# smog_v1_1_brain.net
KiCad netlist of a schematic drawn in EAGLE
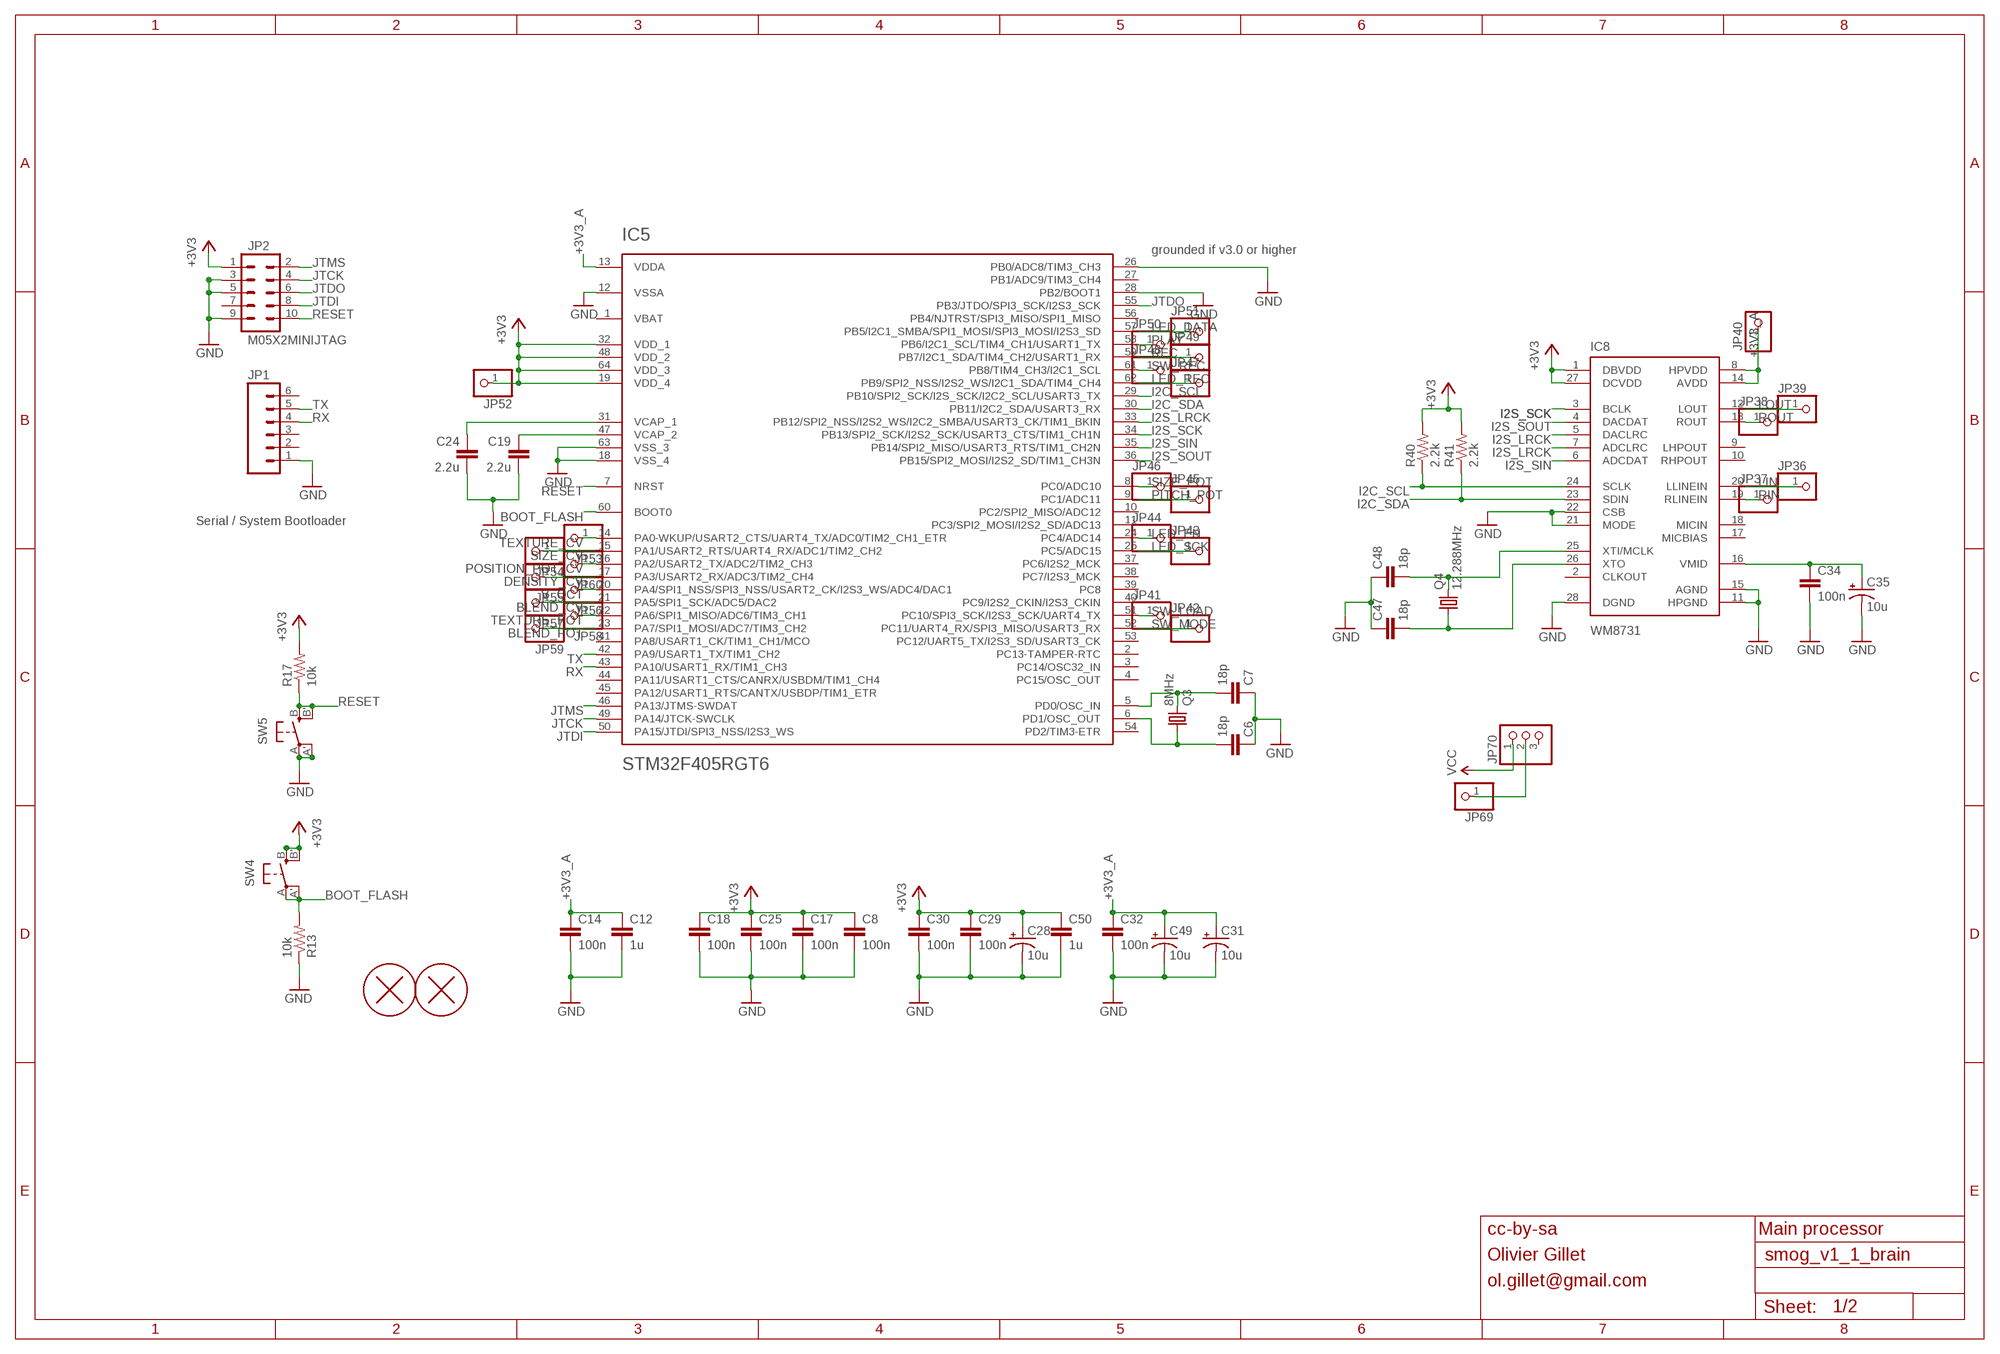
[diagram p0: schematic, sheet 1]
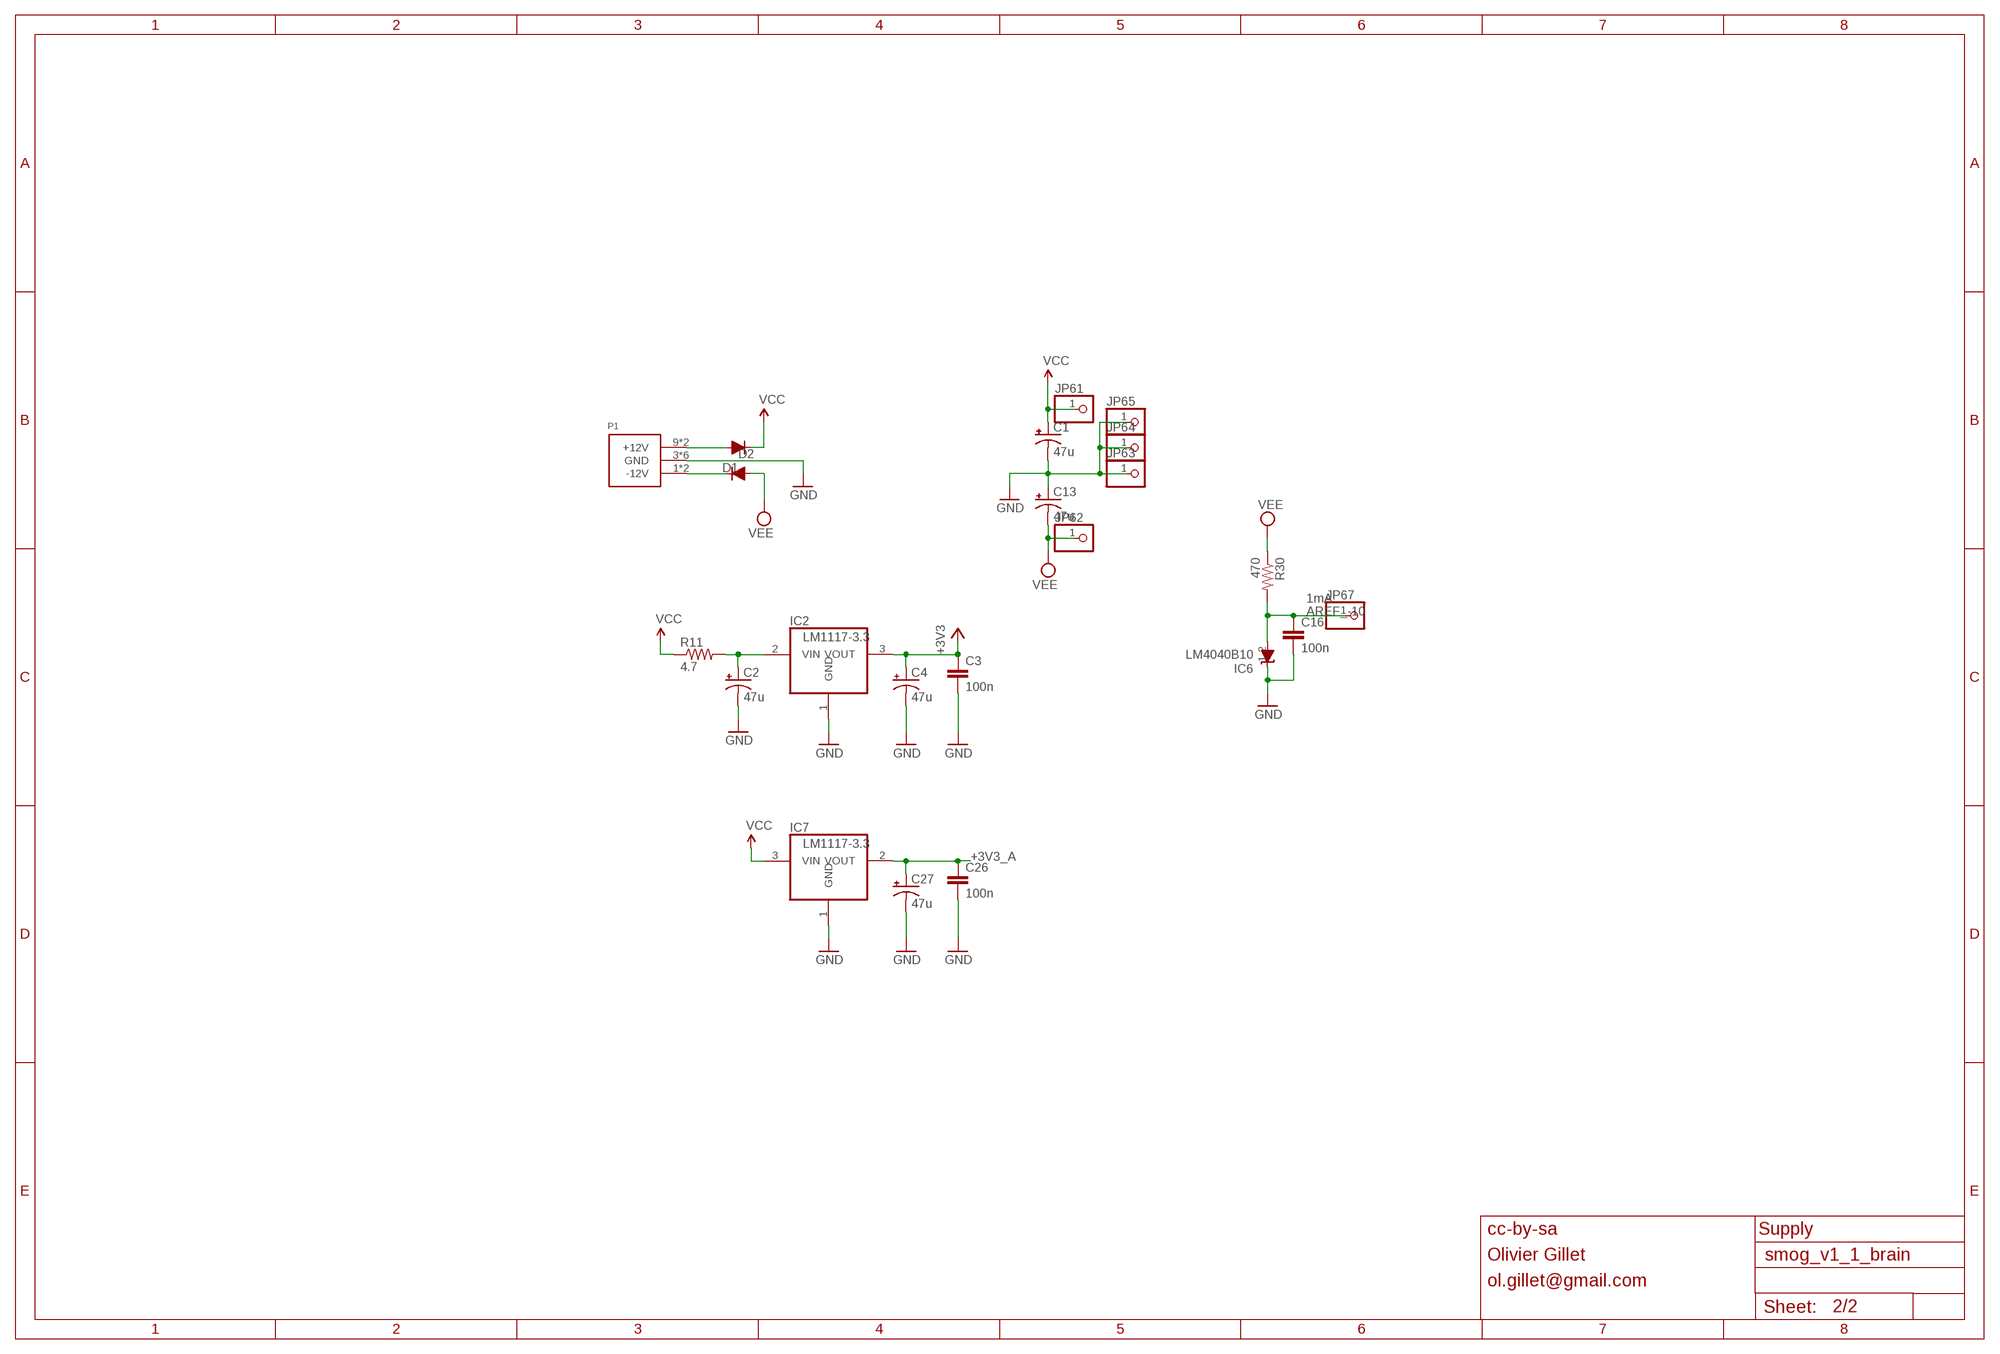
[diagram p1: schematic, sheet 2]

(export (version "E")
  (design (tool "Eeschema 10.0.6"))
  (components
    (comp (ref "C1")
      (value "47u")
      (footprint "eagle-import:PANASONIC_D")
      (libsource (lib "eagle-import") (part "CAP_POLD"))
    )
    (comp (ref "C2")
      (value "47u")
      (footprint "eagle-import:PANASONIC_D")
      (libsource (lib "eagle-import") (part "CAP_POLD"))
    )
    (comp (ref "C3")
      (value "100n")
      (footprint "eagle-import:RESISTOR_0603")
      (libsource (lib "eagle-import") (part "CAPACITOR"))
    )
    (comp (ref "C4")
      (value "47u")
      (footprint "eagle-import:PANASONIC_D")
      (libsource (lib "eagle-import") (part "CAP_POLD"))
    )
    (comp (ref "C13")
      (value "47u")
      (footprint "eagle-import:PANASONIC_D")
      (libsource (lib "eagle-import") (part "CAP_POLD"))
    )
    (comp (ref "C16")
      (value "100n")
      (footprint "eagle-import:RESISTOR_0603")
      (libsource (lib "eagle-import") (part "CAPACITOR"))
    )
    (comp (ref "C26")
      (value "100n")
      (footprint "eagle-import:RESISTOR_0603")
      (libsource (lib "eagle-import") (part "CAPACITOR"))
    )
    (comp (ref "C27")
      (value "47u")
      (footprint "eagle-import:PANASONIC_D")
      (libsource (lib "eagle-import") (part "CAP_POLD"))
    )
    (comp (ref "D1")
      (value "1N5819HW")
      (footprint "eagle-import:SOD123")
      (libsource (lib "eagle-import") (part "DIODE"))
    )
    (comp (ref "D2")
      (value "1N5819HW")
      (footprint "eagle-import:SOD123")
      (libsource (lib "eagle-import") (part "DIODE"))
    )
    (comp (ref "IC2")
      (value "LM1117-3.3")
      (footprint "eagle-import:TO252")
      (libsource (lib "eagle-import") (part "REG1117T"))
    )
    (comp (ref "IC6")
      (value "LM4040B10")
      (footprint "eagle-import:SOT23")
      (libsource (lib "eagle-import") (part "LM4040SOT23"))
    )
    (comp (ref "IC7")
      (value "LM1117-3.3")
      (footprint "eagle-import:SOT223")
      (libsource (lib "eagle-import") (part "REG1117"))
    )
    (comp (ref "JP61")
      (value "PINHD-1X1")
      (footprint "eagle-import:1X01")
      (libsource (lib "eagle-import") (part "PINHD-1X1"))
    )
    (comp (ref "JP62")
      (value "PINHD-1X1")
      (footprint "eagle-import:1X01")
      (libsource (lib "eagle-import") (part "PINHD-1X1"))
    )
    (comp (ref "JP63")
      (value "PINHD-1X1")
      (footprint "eagle-import:1X01")
      (libsource (lib "eagle-import") (part "PINHD-1X1"))
    )
    (comp (ref "JP64")
      (value "PINHD-1X1")
      (footprint "eagle-import:1X01")
      (libsource (lib "eagle-import") (part "PINHD-1X1"))
    )
    (comp (ref "JP65")
      (value "PINHD-1X1")
      (footprint "eagle-import:1X01")
      (libsource (lib "eagle-import") (part "PINHD-1X1"))
    )
    (comp (ref "JP67")
      (value "PINHD-1X1")
      (footprint "eagle-import:1X01")
      (libsource (lib "eagle-import") (part "PINHD-1X1"))
    )
    (comp (ref "P1")
      (value "POWER_SIMPLE10")
      (footprint "eagle-import:POWER_10")
      (libsource (lib "eagle-import") (part "POWER_SIMPLE10"))
    )
    (comp (ref "R11")
      (value "4.7")
      (footprint "eagle-import:RESISTOR_0603")
      (libsource (lib "eagle-import") (part "RESISTOR"))
    )
    (comp (ref "R30")
      (value "470")
      (footprint "eagle-import:RESISTOR_0603")
      (libsource (lib "eagle-import") (part "RESISTOR"))
    )
    (comp (ref "C6")
      (value "18p")
      (footprint "eagle-import:RESISTOR_0603")
      (libsource (lib "eagle-import") (part "CAPACITOR"))
    )
    (comp (ref "C7")
      (value "18p")
      (footprint "eagle-import:RESISTOR_0603")
      (libsource (lib "eagle-import") (part "CAPACITOR"))
    )
    (comp (ref "C8")
      (value "100n")
      (footprint "eagle-import:RESISTOR_0603")
      (libsource (lib "eagle-import") (part "CAPACITOR"))
    )
    (comp (ref "C12")
      (value "1u")
      (footprint "eagle-import:RESISTOR_0603")
      (libsource (lib "eagle-import") (part "CAPACITOR"))
    )
    (comp (ref "C14")
      (value "100n")
      (footprint "eagle-import:RESISTOR_0603")
      (libsource (lib "eagle-import") (part "CAPACITOR"))
    )
    (comp (ref "C17")
      (value "100n")
      (footprint "eagle-import:RESISTOR_0603")
      (libsource (lib "eagle-import") (part "CAPACITOR"))
    )
    (comp (ref "C18")
      (value "100n")
      (footprint "eagle-import:RESISTOR_0603")
      (libsource (lib "eagle-import") (part "CAPACITOR"))
    )
    (comp (ref "C19")
      (value "2.2u")
      (footprint "eagle-import:RESISTOR_0603")
      (libsource (lib "eagle-import") (part "CAPACITOR"))
    )
    (comp (ref "C24")
      (value "2.2u")
      (footprint "eagle-import:RESISTOR_0603")
      (libsource (lib "eagle-import") (part "CAPACITOR"))
    )
    (comp (ref "C25")
      (value "100n")
      (footprint "eagle-import:RESISTOR_0603")
      (libsource (lib "eagle-import") (part "CAPACITOR"))
    )
    (comp (ref "C28")
      (value "10u")
      (footprint "eagle-import:PANASONIC_B")
      (libsource (lib "eagle-import") (part "CAP_POL"))
    )
    (comp (ref "C29")
      (value "100n")
      (footprint "eagle-import:RESISTOR_0603")
      (libsource (lib "eagle-import") (part "CAPACITOR"))
    )
    (comp (ref "C30")
      (value "100n")
      (footprint "eagle-import:RESISTOR_0603")
      (libsource (lib "eagle-import") (part "CAPACITOR"))
    )
    (comp (ref "C31")
      (value "10u")
      (footprint "eagle-import:PANASONIC_B")
      (libsource (lib "eagle-import") (part "CAP_POL"))
    )
    (comp (ref "C32")
      (value "100n")
      (footprint "eagle-import:RESISTOR_0603")
      (libsource (lib "eagle-import") (part "CAPACITOR"))
    )
    (comp (ref "C34")
      (value "100n")
      (footprint "eagle-import:RESISTOR_0603")
      (libsource (lib "eagle-import") (part "CAPACITOR"))
    )
    (comp (ref "C35")
      (value "10u")
      (footprint "eagle-import:PANASONIC_B")
      (libsource (lib "eagle-import") (part "CAP_POL"))
    )
    (comp (ref "C47")
      (value "18p")
      (footprint "eagle-import:RESISTOR_0603")
      (libsource (lib "eagle-import") (part "CAPACITOR"))
    )
    (comp (ref "C48")
      (value "18p")
      (footprint "eagle-import:RESISTOR_0603")
      (libsource (lib "eagle-import") (part "CAPACITOR"))
    )
    (comp (ref "C49")
      (value "10u")
      (footprint "eagle-import:PANASONIC_B")
      (libsource (lib "eagle-import") (part "CAP_POL"))
    )
    (comp (ref "C50")
      (value "1u")
      (footprint "eagle-import:RESISTOR_0603")
      (libsource (lib "eagle-import") (part "CAPACITOR"))
    )
    (comp (ref "H1")
      (value "PCB_SCREW")
      (footprint "eagle-import:PCB_SCREW")
      (libsource (lib "eagle-import") (part "PCB_SCREW"))
    )
    (comp (ref "H2")
      (value "PCB_SCREW")
      (footprint "eagle-import:PCB_SCREW")
      (libsource (lib "eagle-import") (part "PCB_SCREW"))
    )
    (comp (ref "IC5")
      (value "STM32F405RGT6")
      (footprint "eagle-import:TQFP-10X10-64")
      (libsource (lib "eagle-import") (part "STM32F20X"))
    )
    (comp (ref "IC8")
      (value "WM8731")
      (footprint "eagle-import:SSOP28")
      (libsource (lib "eagle-import") (part "WM8731"))
    )
    (comp (ref "JP1")
      (value "M06SIP")
      (footprint "eagle-import:1X06")
      (libsource (lib "eagle-import") (part "M06SIP"))
    )
    (comp (ref "JP2")
      (value "M05X2MINIJTAG")
      (footprint "eagle-import:2X5-1.27")
      (libsource (lib "eagle-import") (part "M05X2MINIJTAG"))
    )
    (comp (ref "JP36")
      (value "PINHD-1X1")
      (footprint "eagle-import:1X01")
      (libsource (lib "eagle-import") (part "PINHD-1X1"))
    )
    (comp (ref "JP37")
      (value "PINHD-1X1")
      (footprint "eagle-import:1X01")
      (libsource (lib "eagle-import") (part "PINHD-1X1"))
    )
    (comp (ref "JP38")
      (value "PINHD-1X1")
      (footprint "eagle-import:1X01")
      (libsource (lib "eagle-import") (part "PINHD-1X1"))
    )
    (comp (ref "JP39")
      (value "PINHD-1X1")
      (footprint "eagle-import:1X01")
      (libsource (lib "eagle-import") (part "PINHD-1X1"))
    )
    (comp (ref "JP40")
      (value "PINHD-1X1")
      (footprint "eagle-import:1X01")
      (libsource (lib "eagle-import") (part "PINHD-1X1"))
    )
    (comp (ref "JP41")
      (value "PINHD-1X1")
      (footprint "eagle-import:1X01")
      (libsource (lib "eagle-import") (part "PINHD-1X1"))
    )
    (comp (ref "JP42")
      (value "PINHD-1X1")
      (footprint "eagle-import:1X01")
      (libsource (lib "eagle-import") (part "PINHD-1X1"))
    )
    (comp (ref "JP43")
      (value "PINHD-1X1")
      (footprint "eagle-import:1X01")
      (libsource (lib "eagle-import") (part "PINHD-1X1"))
    )
    (comp (ref "JP44")
      (value "PINHD-1X1")
      (footprint "eagle-import:1X01")
      (libsource (lib "eagle-import") (part "PINHD-1X1"))
    )
    (comp (ref "JP45")
      (value "PINHD-1X1")
      (footprint "eagle-import:1X01")
      (libsource (lib "eagle-import") (part "PINHD-1X1"))
    )
    (comp (ref "JP46")
      (value "PINHD-1X1")
      (footprint "eagle-import:1X01")
      (libsource (lib "eagle-import") (part "PINHD-1X1"))
    )
    (comp (ref "JP47")
      (value "PINHD-1X1")
      (footprint "eagle-import:1X01")
      (libsource (lib "eagle-import") (part "PINHD-1X1"))
    )
    (comp (ref "JP48")
      (value "PINHD-1X1")
      (footprint "eagle-import:1X01")
      (libsource (lib "eagle-import") (part "PINHD-1X1"))
    )
    (comp (ref "JP49")
      (value "PINHD-1X1")
      (footprint "eagle-import:1X01")
      (libsource (lib "eagle-import") (part "PINHD-1X1"))
    )
    (comp (ref "JP50")
      (value "PINHD-1X1")
      (footprint "eagle-import:1X01")
      (libsource (lib "eagle-import") (part "PINHD-1X1"))
    )
    (comp (ref "JP51")
      (value "PINHD-1X1")
      (footprint "eagle-import:1X01")
      (libsource (lib "eagle-import") (part "PINHD-1X1"))
    )
    (comp (ref "JP52")
      (value "PINHD-1X1")
      (footprint "eagle-import:1X01")
      (libsource (lib "eagle-import") (part "PINHD-1X1"))
    )
    (comp (ref "JP53")
      (value "PINHD-1X1")
      (footprint "eagle-import:1X01")
      (libsource (lib "eagle-import") (part "PINHD-1X1"))
    )
    (comp (ref "JP54")
      (value "PINHD-1X1")
      (footprint "eagle-import:1X01")
      (libsource (lib "eagle-import") (part "PINHD-1X1"))
    )
    (comp (ref "JP55")
      (value "PINHD-1X1")
      (footprint "eagle-import:1X01")
      (libsource (lib "eagle-import") (part "PINHD-1X1"))
    )
    (comp (ref "JP56")
      (value "PINHD-1X1")
      (footprint "eagle-import:1X01")
      (libsource (lib "eagle-import") (part "PINHD-1X1"))
    )
    (comp (ref "JP57")
      (value "PINHD-1X1")
      (footprint "eagle-import:1X01")
      (libsource (lib "eagle-import") (part "PINHD-1X1"))
    )
    (comp (ref "JP58")
      (value "PINHD-1X1")
      (footprint "eagle-import:1X01")
      (libsource (lib "eagle-import") (part "PINHD-1X1"))
    )
    (comp (ref "JP59")
      (value "PINHD-1X1")
      (footprint "eagle-import:1X01")
      (libsource (lib "eagle-import") (part "PINHD-1X1"))
    )
    (comp (ref "JP60")
      (value "PINHD-1X1")
      (footprint "eagle-import:1X01")
      (libsource (lib "eagle-import") (part "PINHD-1X1"))
    )
    (comp (ref "JP69")
      (value "PINHD-1X1")
      (footprint "eagle-import:1X01")
      (libsource (lib "eagle-import") (part "PINHD-1X1"))
    )
    (comp (ref "JP70")
      (value "PINHD-1X3")
      (footprint "eagle-import:1X03")
      (libsource (lib "eagle-import") (part "PINHD-1X3"))
    )
    (comp (ref "Q3")
      (value "8MHz")
      (footprint "eagle-import:HC49UP")
      (libsource (lib "eagle-import") (part "CRYSTAL"))
    )
    (comp (ref "Q4")
      (value "12.288MHz")
      (footprint "eagle-import:HC49UP")
      (libsource (lib "eagle-import") (part "CRYSTAL"))
    )
    (comp (ref "R13")
      (value "10k")
      (footprint "eagle-import:RESISTOR_0603")
      (libsource (lib "eagle-import") (part "RESISTOR"))
    )
    (comp (ref "R17")
      (value "10k")
      (footprint "eagle-import:RESISTOR_0603")
      (libsource (lib "eagle-import") (part "RESISTOR"))
    )
    (comp (ref "R40")
      (value "2.2k")
      (footprint "eagle-import:RESISTOR_0603")
      (libsource (lib "eagle-import") (part "RESISTOR"))
    )
    (comp (ref "R41")
      (value "2.2k")
      (footprint "eagle-import:RESISTOR_0603")
      (libsource (lib "eagle-import") (part "RESISTOR"))
    )
    (comp (ref "SW4")
      (value "EVQQ2")
      (footprint "eagle-import:EVQ-Q2")
      (libsource (lib "eagle-import") (part "EVQQ2"))
    )
    (comp (ref "SW5")
      (value "EVQQ2")
      (footprint "eagle-import:EVQ-Q2")
      (libsource (lib "eagle-import") (part "EVQQ2"))
    )
  )
  (nets
    (net (code "1") (name "+3V3") (class "Default")
      (node (ref "C17") (pin "1") (pinfunction "1_1") (pintype "passive"))
      (node (ref "C18") (pin "1") (pinfunction "1_1") (pintype "passive"))
      (node (ref "C25") (pin "1") (pinfunction "1_1") (pintype "passive"))
      (node (ref "C28") (pin "+") (pinfunction "+_+") (pintype "passive"))
      (node (ref "C29") (pin "1") (pinfunction "1_1") (pintype "passive"))
      (node (ref "C3") (pin "1") (pinfunction "1_1") (pintype "passive"))
      (node (ref "C30") (pin "1") (pinfunction "1_1") (pintype "passive"))
      (node (ref "C4") (pin "+") (pinfunction "+_+") (pintype "passive"))
      (node (ref "C50") (pin "1") (pinfunction "1_1") (pintype "passive"))
      (node (ref "C8") (pin "1") (pinfunction "1_1") (pintype "passive"))
      (node (ref "IC2") (pin "3") (pinfunction "VOUT_3") (pintype "output"))
      (node (ref "IC5") (pin "19") (pinfunction "VDD_4_19") (pintype "power_in"))
      (node (ref "IC5") (pin "32") (pinfunction "VDD_1_32") (pintype "power_in"))
      (node (ref "IC5") (pin "48") (pinfunction "VDD_2_48") (pintype "power_in"))
      (node (ref "IC5") (pin "64") (pinfunction "VDD_3_64") (pintype "power_in"))
      (node (ref "IC8") (pin "1") (pinfunction "DBVDD_1") (pintype "bidirectional"))
      (node (ref "IC8") (pin "27") (pinfunction "DCVDD_27") (pintype "bidirectional"))
      (node (ref "JP2") (pin "1") (pinfunction "1_1") (pintype "passive"))
      (node (ref "JP52") (pin "1") (pinfunction "1_1") (pintype "passive"))
      (node (ref "R17") (pin "2") (pinfunction "2_2") (pintype "passive"))
      (node (ref "R40") (pin "2") (pinfunction "2_2") (pintype "passive"))
      (node (ref "R41") (pin "2") (pinfunction "2_2") (pintype "passive"))
      (node (ref "SW4") (pin "B") (pinfunction "S_B") (pintype "passive"))
      (node (ref "SW4") (pin "B'") (pinfunction "S1_B'") (pintype "passive"))
    )
    (net (code "2") (name "+3V3_A") (class "Default")
      (node (ref "C12") (pin "1") (pinfunction "1_1") (pintype "passive"))
      (node (ref "C14") (pin "1") (pinfunction "1_1") (pintype "passive"))
      (node (ref "C26") (pin "1") (pinfunction "1_1") (pintype "passive"))
      (node (ref "C27") (pin "+") (pinfunction "+_+") (pintype "passive"))
      (node (ref "C31") (pin "+") (pinfunction "+_+") (pintype "passive"))
      (node (ref "C32") (pin "1") (pinfunction "1_1") (pintype "passive"))
      (node (ref "C49") (pin "+") (pinfunction "+_+") (pintype "passive"))
      (node (ref "IC5") (pin "13") (pinfunction "VDDA_13") (pintype "power_in"))
      (node (ref "IC7") (pin "2") (pinfunction "VOUT_2") (pintype "output"))
      (node (ref "IC8") (pin "14") (pinfunction "AVDD_14") (pintype "bidirectional"))
      (node (ref "IC8") (pin "8") (pinfunction "HPVDD_8") (pintype "bidirectional"))
      (node (ref "JP40") (pin "1") (pinfunction "1_1") (pintype "passive"))
    )
    (net (code "3") (name "AREF_-10") (class "Default")
      (node (ref "C16") (pin "1") (pinfunction "1_1") (pintype "passive"))
      (node (ref "IC6") (pin "2") (pinfunction "A_2") (pintype "passive"))
      (node (ref "JP67") (pin "1") (pinfunction "1_1") (pintype "passive"))
      (node (ref "R30") (pin "2") (pinfunction "2_2") (pintype "passive"))
    )
    (net (code "4") (name "BLEND_CV") (class "Default")
      (node (ref "IC5") (pin "21") (pinfunction "PA5/SPI1_SCK/ADC5/DAC2_21") (pintype "bidirectional"))
      (node (ref "JP57") (pin "1") (pinfunction "1_1") (pintype "passive"))
    )
    (net (code "5") (name "BLEND_POT") (class "Default")
      (node (ref "IC5") (pin "23") (pinfunction "PA7/SPI1_MOSI/ADC7/TIM3_CH2_23") (pintype "bidirectional"))
      (node (ref "JP59") (pin "1") (pinfunction "1_1") (pintype "passive"))
    )
    (net (code "6") (name "BOOT_FLASH") (class "Default")
      (node (ref "IC5") (pin "60") (pinfunction "BOOT0_60") (pintype "bidirectional"))
      (node (ref "R13") (pin "2") (pinfunction "2_2") (pintype "passive"))
      (node (ref "SW4") (pin "A") (pinfunction "P_A") (pintype "passive"))
      (node (ref "SW4") (pin "A'") (pinfunction "P1_A'") (pintype "passive"))
    )
    (net (code "7") (name "DENSITY_CV") (class "Default")
      (node (ref "IC5") (pin "17") (pinfunction "PA3/USART2_RX/ADC3/TIM2_CH4_17") (pintype "bidirectional"))
      (node (ref "JP55") (pin "1") (pinfunction "1_1") (pintype "passive"))
    )
    (net (code "8") (name "GND") (class "Default")
      (node (ref "C1") (pin "-") (pinfunction "-_-") (pintype "passive"))
      (node (ref "C12") (pin "2") (pinfunction "2_2") (pintype "passive"))
      (node (ref "C13") (pin "+") (pinfunction "+_+") (pintype "passive"))
      (node (ref "C14") (pin "2") (pinfunction "2_2") (pintype "passive"))
      (node (ref "C16") (pin "2") (pinfunction "2_2") (pintype "passive"))
      (node (ref "C17") (pin "2") (pinfunction "2_2") (pintype "passive"))
      (node (ref "C18") (pin "2") (pinfunction "2_2") (pintype "passive"))
      (node (ref "C19") (pin "2") (pinfunction "2_2") (pintype "passive"))
      (node (ref "C2") (pin "-") (pinfunction "-_-") (pintype "passive"))
      (node (ref "C24") (pin "2") (pinfunction "2_2") (pintype "passive"))
      (node (ref "C25") (pin "2") (pinfunction "2_2") (pintype "passive"))
      (node (ref "C26") (pin "2") (pinfunction "2_2") (pintype "passive"))
      (node (ref "C27") (pin "-") (pinfunction "-_-") (pintype "passive"))
      (node (ref "C28") (pin "-") (pinfunction "-_-") (pintype "passive"))
      (node (ref "C29") (pin "2") (pinfunction "2_2") (pintype "passive"))
      (node (ref "C3") (pin "2") (pinfunction "2_2") (pintype "passive"))
      (node (ref "C30") (pin "2") (pinfunction "2_2") (pintype "passive"))
      (node (ref "C31") (pin "-") (pinfunction "-_-") (pintype "passive"))
      (node (ref "C32") (pin "2") (pinfunction "2_2") (pintype "passive"))
      (node (ref "C34") (pin "2") (pinfunction "2_2") (pintype "passive"))
      (node (ref "C35") (pin "-") (pinfunction "-_-") (pintype "passive"))
      (node (ref "C4") (pin "-") (pinfunction "-_-") (pintype "passive"))
      (node (ref "C47") (pin "1") (pinfunction "1_1") (pintype "passive"))
      (node (ref "C48") (pin "1") (pinfunction "1_1") (pintype "passive"))
      (node (ref "C49") (pin "-") (pinfunction "-_-") (pintype "passive"))
      (node (ref "C50") (pin "2") (pinfunction "2_2") (pintype "passive"))
      (node (ref "C6") (pin "1") (pinfunction "1_1") (pintype "passive"))
      (node (ref "C7") (pin "1") (pinfunction "1_1") (pintype "passive"))
      (node (ref "C8") (pin "2") (pinfunction "2_2") (pintype "passive"))
      (node (ref "IC2") (pin "1") (pinfunction "GND_1") (pintype "power_in"))
      (node (ref "IC5") (pin "12") (pinfunction "VSSA_12") (pintype "power_in"))
      (node (ref "IC5") (pin "18") (pinfunction "VSS_4_18") (pintype "power_in"))
      (node (ref "IC5") (pin "26") (pinfunction "PB0/ADC8/TIM3_CH3_26") (pintype "bidirectional"))
      (node (ref "IC5") (pin "28") (pinfunction "PB2/BOOT1_28") (pintype "bidirectional"))
      (node (ref "IC5") (pin "63") (pinfunction "VSS_3_63") (pintype "power_in"))
      (node (ref "IC6") (pin "1") (pinfunction "C_1") (pintype "passive"))
      (node (ref "IC7") (pin "1") (pinfunction "GND_1") (pintype "power_in"))
      (node (ref "IC8") (pin "11") (pinfunction "HPGND_11") (pintype "bidirectional"))
      (node (ref "IC8") (pin "15") (pinfunction "AGND_15") (pintype "bidirectional"))
      (node (ref "IC8") (pin "21") (pinfunction "MODE_21") (pintype "bidirectional"))
      (node (ref "IC8") (pin "22") (pinfunction "CSB_22") (pintype "bidirectional"))
      (node (ref "IC8") (pin "28") (pinfunction "DGND_28") (pintype "bidirectional"))
      (node (ref "JP1") (pin "1") (pinfunction "1_1") (pintype "passive"))
      (node (ref "JP2") (pin "3") (pinfunction "3_3") (pintype "passive"))
      (node (ref "JP2") (pin "5") (pinfunction "5_5") (pintype "passive"))
      (node (ref "JP2") (pin "9") (pinfunction "9_9") (pintype "passive"))
      (node (ref "JP63") (pin "1") (pinfunction "1_1") (pintype "passive"))
      (node (ref "JP64") (pin "1") (pinfunction "1_1") (pintype "passive"))
      (node (ref "JP65") (pin "1") (pinfunction "1_1") (pintype "passive"))
      (node (ref "P1") (pin "3") (pinfunction "GND_3") (pintype "bidirectional"))
      (node (ref "P1") (pin "4") (pinfunction "GND_4") (pintype "bidirectional"))
      (node (ref "P1") (pin "5") (pinfunction "GND_5") (pintype "bidirectional"))
      (node (ref "P1") (pin "6") (pinfunction "GND_6") (pintype "bidirectional"))
      (node (ref "P1") (pin "7") (pinfunction "GND_7") (pintype "bidirectional"))
      (node (ref "P1") (pin "8") (pinfunction "GND_8") (pintype "bidirectional"))
      (node (ref "R13") (pin "1") (pinfunction "1_1") (pintype "passive"))
      (node (ref "SW5") (pin "A") (pinfunction "P_A") (pintype "passive"))
      (node (ref "SW5") (pin "A'") (pinfunction "P1_A'") (pintype "passive"))
    )
    (net (code "9") (name "I2C_SCL") (class "Default")
      (node (ref "IC5") (pin "29") (pinfunction "PB10/SPI2_SCK/I2S_SCK/I2C2_SCL/USART3_TX_29") (pintype "bidirectional"))
      (node (ref "IC8") (pin "24") (pinfunction "SCLK_24") (pintype "bidirectional"))
      (node (ref "R40") (pin "1") (pinfunction "1_1") (pintype "passive"))
    )
    (net (code "10") (name "I2C_SDA") (class "Default")
      (node (ref "IC5") (pin "30") (pinfunction "PB11/I2C2_SDA/USART3_RX_30") (pintype "bidirectional"))
      (node (ref "IC8") (pin "23") (pinfunction "SDIN_23") (pintype "bidirectional"))
      (node (ref "R41") (pin "1") (pinfunction "1_1") (pintype "passive"))
    )
    (net (code "11") (name "I2S_LRCK") (class "Default")
      (node (ref "IC5") (pin "33") (pinfunction "PB12/SPI2_NSS/I2S2_WS/I2C2_SMBA/USART3_CK/TIM1_BKIN_33") (pintype "bidirectional"))
      (node (ref "IC8") (pin "5") (pinfunction "DACLRC_5") (pintype "bidirectional"))
      (node (ref "IC8") (pin "7") (pinfunction "ADCLRC_7") (pintype "bidirectional"))
    )
    (net (code "12") (name "I2S_SCK") (class "Default")
      (node (ref "IC5") (pin "34") (pinfunction "PB13/SPI2_SCK/I2S2_SCK/USART3_CTS/TIM1_CH1N_34") (pintype "bidirectional"))
      (node (ref "IC8") (pin "3") (pinfunction "BCLK_3") (pintype "bidirectional"))
    )
    (net (code "13") (name "I2S_SIN") (class "Default")
      (node (ref "IC5") (pin "35") (pinfunction "PB14/SPI2_MISO/USART3_RTS/TIM1_CH2N_35") (pintype "bidirectional"))
      (node (ref "IC8") (pin "6") (pinfunction "ADCDAT_6") (pintype "bidirectional"))
    )
    (net (code "14") (name "I2S_SOUT") (class "Default")
      (node (ref "IC5") (pin "36") (pinfunction "PB15/SPI2_MOSI/I2S2_SD/TIM1_CH3N_36") (pintype "bidirectional"))
      (node (ref "IC8") (pin "4") (pinfunction "DACDAT_4") (pintype "bidirectional"))
    )
    (net (code "15") (name "JTCK") (class "Default")
      (node (ref "IC5") (pin "49") (pinfunction "PA14/JTCK-SWCLK_49") (pintype "bidirectional"))
      (node (ref "JP2") (pin "4") (pinfunction "4_4") (pintype "passive"))
    )
    (net (code "16") (name "JTDI") (class "Default")
      (node (ref "IC5") (pin "50") (pinfunction "PA15/JTDI/SPI3_NSS/I2S3_WS_50") (pintype "bidirectional"))
      (node (ref "JP2") (pin "8") (pinfunction "8_8") (pintype "passive"))
    )
    (net (code "17") (name "JTDO") (class "Default")
      (node (ref "IC5") (pin "55") (pinfunction "PB3/JTDO/SPI3_SCK/I2S3_SCK_55") (pintype "bidirectional"))
      (node (ref "JP2") (pin "6") (pinfunction "6_6") (pintype "passive"))
    )
    (net (code "18") (name "JTMS") (class "Default")
      (node (ref "IC5") (pin "46") (pinfunction "PA13/JTMS-SWDAT_46") (pintype "bidirectional"))
      (node (ref "JP2") (pin "2") (pinfunction "2_2") (pintype "passive"))
    )
    (net (code "19") (name "LED_DATA") (class "Default")
      (node (ref "IC5") (pin "57") (pinfunction "PB5/I2C1_SMBA/SPI1_MOSI/SPI3_MOSI/I2S3_SD_57") (pintype "bidirectional"))
      (node (ref "JP51") (pin "1") (pinfunction "1_1") (pintype "passive"))
    )
    (net (code "20") (name "LED_EN") (class "Default")
      (node (ref "IC5") (pin "24") (pinfunction "PC4/ADC14_24") (pintype "bidirectional"))
      (node (ref "JP44") (pin "1") (pinfunction "1_1") (pintype "passive"))
    )
    (net (code "21") (name "LED_REC") (class "Default")
      (node (ref "IC5") (pin "62") (pinfunction "PB9/SPI2_NSS/I2S2_WS/I2C1_SDA/TIM4_CH4_62") (pintype "bidirectional"))
      (node (ref "JP47") (pin "1") (pinfunction "1_1") (pintype "passive"))
    )
    (net (code "22") (name "LED_SCK") (class "Default")
      (node (ref "IC5") (pin "25") (pinfunction "PC5/ADC15_25") (pintype "bidirectional"))
      (node (ref "JP43") (pin "1") (pinfunction "1_1") (pintype "passive"))
    )
    (net (code "23") (name "LIN") (class "Default")
      (node (ref "IC8") (pin "20") (pinfunction "LLINEIN_20") (pintype "bidirectional"))
      (node (ref "JP36") (pin "1") (pinfunction "1_1") (pintype "passive"))
    )
    (net (code "24") (name "LOUT") (class "Default")
      (node (ref "IC8") (pin "12") (pinfunction "LOUT_12") (pintype "bidirectional"))
      (node (ref "JP39") (pin "1") (pinfunction "1_1") (pintype "passive"))
    )
    (net (code "25") (name "Net-(D1-Pad+)") (class "Default")
      (node (ref "D1") (pin "+") (pinfunction "+_+") (pintype "passive"))
      (node (ref "P1") (pin "10") (pinfunction "+12V_10") (pintype "bidirectional"))
      (node (ref "P1") (pin "9") (pinfunction "+12V_9") (pintype "bidirectional"))
    )
    (net (code "26") (name "Net-(D2-Pad-)") (class "Default")
      (node (ref "D2") (pin "-") (pinfunction "-_-") (pintype "passive"))
      (node (ref "P1") (pin "1") (pinfunction "-12V_1") (pintype "bidirectional"))
      (node (ref "P1") (pin "2") (pinfunction "-12V_2") (pintype "bidirectional"))
    )
    (net (code "27") (name "Net-(IC2-VIN)") (class "Default")
      (node (ref "C2") (pin "+") (pinfunction "+_+") (pintype "passive"))
      (node (ref "IC2") (pin "2") (pinfunction "VIN_2") (pintype "input"))
      (node (ref "R11") (pin "2") (pinfunction "2_2") (pintype "passive"))
    )
    (net (code "28") (name "Net-(IC5-PD0{slash}OSC_IN)") (class "Default")
      (node (ref "C7") (pin "2") (pinfunction "2_2") (pintype "passive"))
      (node (ref "IC5") (pin "5") (pinfunction "PD0/OSC_IN_5") (pintype "bidirectional"))
      (node (ref "Q3") (pin "2") (pinfunction "2_2") (pintype "passive"))
    )
    (net (code "29") (name "Net-(IC5-PD1{slash}OSC_OUT)") (class "Default")
      (node (ref "C6") (pin "2") (pinfunction "2_2") (pintype "passive"))
      (node (ref "IC5") (pin "6") (pinfunction "PD1/OSC_OUT_6") (pintype "bidirectional"))
      (node (ref "Q3") (pin "1") (pinfunction "1_1") (pintype "passive"))
    )
    (net (code "30") (name "Net-(IC5-VCAP_1)") (class "Default")
      (node (ref "C24") (pin "1") (pinfunction "1_1") (pintype "passive"))
      (node (ref "IC5") (pin "31") (pinfunction "VCAP_1_31") (pintype "power_in"))
    )
    (net (code "31") (name "Net-(IC5-VCAP_2)") (class "Default")
      (node (ref "C19") (pin "1") (pinfunction "1_1") (pintype "passive"))
      (node (ref "IC5") (pin "47") (pinfunction "VCAP_2_47") (pintype "power_in"))
    )
    (net (code "32") (name "Net-(IC8-VMID)") (class "Default")
      (node (ref "C34") (pin "1") (pinfunction "1_1") (pintype "passive"))
      (node (ref "C35") (pin "+") (pinfunction "+_+") (pintype "passive"))
      (node (ref "IC8") (pin "16") (pinfunction "VMID_16") (pintype "bidirectional"))
    )
    (net (code "33") (name "Net-(IC8-XTI{slash}MCLK)") (class "Default")
      (node (ref "C48") (pin "2") (pinfunction "2_2") (pintype "passive"))
      (node (ref "IC8") (pin "25") (pinfunction "XTI/MCLK_25") (pintype "bidirectional"))
      (node (ref "Q4") (pin "2") (pinfunction "2_2") (pintype "passive"))
    )
    (net (code "34") (name "Net-(IC8-XTO)") (class "Default")
      (node (ref "C47") (pin "2") (pinfunction "2_2") (pintype "passive"))
      (node (ref "IC8") (pin "26") (pinfunction "XTO_26") (pintype "bidirectional"))
      (node (ref "Q4") (pin "1") (pinfunction "1_1") (pintype "passive"))
    )
    (net (code "35") (name "Net-(JP69-Pad1)") (class "Default")
      (node (ref "JP69") (pin "1") (pinfunction "1_1") (pintype "passive"))
      (node (ref "JP70") (pin "2") (pinfunction "2_2") (pintype "passive"))
    )
    (net (code "36") (name "PITCH_POT") (class "Default")
      (node (ref "IC5") (pin "9") (pinfunction "PC1/ADC11_9") (pintype "bidirectional"))
      (node (ref "JP45") (pin "1") (pinfunction "1_1") (pintype "passive"))
    )
    (net (code "37") (name "PLAY") (class "Default")
      (node (ref "IC5") (pin "58") (pinfunction "PB6/I2C1_SCL/TIM4_CH1/USART1_TX_58") (pintype "bidirectional"))
      (node (ref "JP50") (pin "1") (pinfunction "1_1") (pintype "passive"))
    )
    (net (code "38") (name "POSITION_POT_CV") (class "Default")
      (node (ref "IC5") (pin "16") (pinfunction "PA2/USART2_TX/ADC2/TIM2_CH3_16") (pintype "bidirectional"))
      (node (ref "JP60") (pin "1") (pinfunction "1_1") (pintype "passive"))
    )
    (net (code "39") (name "REC") (class "Default")
      (node (ref "IC5") (pin "59") (pinfunction "PB7/I2C1_SDA/TIM4_CH2/USART1_RX_59") (pintype "bidirectional"))
      (node (ref "JP49") (pin "1") (pinfunction "1_1") (pintype "passive"))
    )
    (net (code "40") (name "RESET") (class "Default")
      (node (ref "IC5") (pin "7") (pinfunction "NRST_7") (pintype "bidirectional"))
      (node (ref "JP2") (pin "10") (pinfunction "10_10") (pintype "passive"))
      (node (ref "R17") (pin "1") (pinfunction "1_1") (pintype "passive"))
      (node (ref "SW5") (pin "B") (pinfunction "S_B") (pintype "passive"))
      (node (ref "SW5") (pin "B'") (pinfunction "S1_B'") (pintype "passive"))
    )
    (net (code "41") (name "RIN") (class "Default")
      (node (ref "IC8") (pin "19") (pinfunction "RLINEIN_19") (pintype "bidirectional"))
      (node (ref "JP37") (pin "1") (pinfunction "1_1") (pintype "passive"))
    )
    (net (code "42") (name "ROUT") (class "Default")
      (node (ref "IC8") (pin "13") (pinfunction "ROUT_13") (pintype "bidirectional"))
      (node (ref "JP38") (pin "1") (pinfunction "1_1") (pintype "passive"))
    )
    (net (code "43") (name "RX") (class "Default")
      (node (ref "IC5") (pin "43") (pinfunction "PA10/USART1_RX/TIM1_CH3_43") (pintype "bidirectional"))
      (node (ref "JP1") (pin "4") (pinfunction "4_4") (pintype "passive"))
    )
    (net (code "44") (name "SIZE_CV") (class "Default")
      (node (ref "IC5") (pin "15") (pinfunction "PA1/USART2_RTS/UART4_RX/ADC1/TIM2_CH2_15") (pintype "bidirectional"))
      (node (ref "JP54") (pin "1") (pinfunction "1_1") (pintype "passive"))
    )
    (net (code "45") (name "SIZE_POT") (class "Default")
      (node (ref "IC5") (pin "8") (pinfunction "PC0/ADC10_8") (pintype "bidirectional"))
      (node (ref "JP46") (pin "1") (pinfunction "1_1") (pintype "passive"))
    )
    (net (code "46") (name "SW_LOAD") (class "Default")
      (node (ref "IC5") (pin "51") (pinfunction "PC10/SPI3_SCK/I2S3_SCK/UART4_TX_51") (pintype "bidirectional"))
      (node (ref "JP41") (pin "1") (pinfunction "1_1") (pintype "passive"))
    )
    (net (code "47") (name "SW_MODE") (class "Default")
      (node (ref "IC5") (pin "52") (pinfunction "PC11/UART4_RX/SPI3_MISO/USART3_RX_52") (pintype "bidirectional"))
      (node (ref "JP42") (pin "1") (pinfunction "1_1") (pintype "passive"))
    )
    (net (code "48") (name "SW_REC") (class "Default")
      (node (ref "IC5") (pin "61") (pinfunction "PB8/TIM4_CH3/I2C1_SCL_61") (pintype "bidirectional"))
      (node (ref "JP48") (pin "1") (pinfunction "1_1") (pintype "passive"))
    )
    (net (code "49") (name "TEXTURE_CV") (class "Default")
      (node (ref "IC5") (pin "14") (pinfunction "PA0-WKUP/USART2_CTS/UART4_TX/ADC0/TIM2_CH1_ETR_14") (pintype "bidirectional"))
      (node (ref "JP53") (pin "1") (pinfunction "1_1") (pintype "passive"))
    )
    (net (code "50") (name "TEXTURE_POT") (class "Default")
      (node (ref "IC5") (pin "22") (pinfunction "PA6/SPI1_MISO/ADC6/TIM3_CH1_22") (pintype "bidirectional"))
      (node (ref "JP58") (pin "1") (pinfunction "1_1") (pintype "passive"))
    )
    (net (code "51") (name "TX") (class "Default")
      (node (ref "IC5") (pin "42") (pinfunction "PA9/USART1_TX/TIM1_CH2_42") (pintype "bidirectional"))
      (node (ref "JP1") (pin "5") (pinfunction "5_5") (pintype "passive"))
    )
    (net (code "52") (name "VBAT") (class "Default")
      (node (ref "IC5") (pin "1") (pinfunction "VBAT_1") (pintype "power_in"))
    )
    (net (code "53") (name "VCC") (class "Default")
      (node (ref "C1") (pin "+") (pinfunction "+_+") (pintype "passive"))
      (node (ref "D1") (pin "-") (pinfunction "-_-") (pintype "passive"))
      (node (ref "IC7") (pin "3") (pinfunction "VIN_3") (pintype "input"))
      (node (ref "JP61") (pin "1") (pinfunction "1_1") (pintype "passive"))
      (node (ref "JP70") (pin "1") (pinfunction "1_1") (pintype "passive"))
      (node (ref "R11") (pin "1") (pinfunction "1_1") (pintype "passive"))
    )
    (net (code "54") (name "VEE") (class "Default")
      (node (ref "C13") (pin "-") (pinfunction "-_-") (pintype "passive"))
      (node (ref "D2") (pin "+") (pinfunction "+_+") (pintype "passive"))
      (node (ref "JP62") (pin "1") (pinfunction "1_1") (pintype "passive"))
      (node (ref "R30") (pin "1") (pinfunction "1_1") (pintype "passive"))
    )
    (net (code "55") (name "V_OCT") (class "Default")
      (node (ref "IC5") (pin "20") (pinfunction "PA4/SPI1_NSS/SPI3_NSS/USART2_CK/I2S3_WS/ADC4/DAC1_20") (pintype "bidirectional"))
      (node (ref "JP56") (pin "1") (pinfunction "1_1") (pintype "passive"))
    )
    (net (code "56") (name "unconnected-(IC5-PA8{slash}USART1_CK{slash}TIM1_CH1{slash}MCO-Pad41)") (class "Default")
      (node (ref "IC5") (pin "41") (pinfunction "PA8/USART1_CK/TIM1_CH1/MCO_41") (pintype "bidirectional"))
    )
    (net (code "57") (name "unconnected-(IC5-PA11{slash}USART1_CTS{slash}CANRX{slash}USBDM{slash}TIM1_CH4-Pad44)") (class "Default")
      (node (ref "IC5") (pin "44") (pinfunction "PA11/USART1_CTS/CANRX/USBDM/TIM1_CH4_44") (pintype "bidirectional"))
    )
    (net (code "58") (name "unconnected-(IC5-PA12{slash}USART1_RTS{slash}CANTX{slash}USBDP{slash}TIM1_ETR-Pad45)") (class "Default")
      (node (ref "IC5") (pin "45") (pinfunction "PA12/USART1_RTS/CANTX/USBDP/TIM1_ETR_45") (pintype "bidirectional"))
    )
    (net (code "59") (name "unconnected-(IC5-PB1{slash}ADC9{slash}TIM3_CH4-Pad27)") (class "Default")
      (node (ref "IC5") (pin "27") (pinfunction "PB1/ADC9/TIM3_CH4_27") (pintype "bidirectional"))
    )
    (net (code "60") (name "unconnected-(IC5-PB4{slash}NJTRST{slash}SPI3_MISO{slash}SPI1_MISO-Pad56)") (class "Default")
      (node (ref "IC5") (pin "56") (pinfunction "PB4/NJTRST/SPI3_MISO/SPI1_MISO_56") (pintype "bidirectional"))
    )
    (net (code "61") (name "unconnected-(IC5-PC2{slash}SPI2_MISO{slash}ADC12-Pad10)") (class "Default")
      (node (ref "IC5") (pin "10") (pinfunction "PC2/SPI2_MISO/ADC12_10") (pintype "bidirectional"))
    )
    (net (code "62") (name "unconnected-(IC5-PC3{slash}SPI2_MOSI{slash}I2S2_SD{slash}ADC13-Pad11)") (class "Default")
      (node (ref "IC5") (pin "11") (pinfunction "PC3/SPI2_MOSI/I2S2_SD/ADC13_11") (pintype "bidirectional"))
    )
    (net (code "63") (name "unconnected-(IC5-PC6{slash}I2S2_MCK-Pad37)") (class "Default")
      (node (ref "IC5") (pin "37") (pinfunction "PC6/I2S2_MCK_37") (pintype "bidirectional"))
    )
    (net (code "64") (name "unconnected-(IC5-PC7{slash}I2S3_MCK-Pad38)") (class "Default")
      (node (ref "IC5") (pin "38") (pinfunction "PC7/I2S3_MCK_38") (pintype "bidirectional"))
    )
    (net (code "65") (name "unconnected-(IC5-PC8-Pad39)") (class "Default")
      (node (ref "IC5") (pin "39") (pinfunction "PC8_39") (pintype "bidirectional"))
    )
    (net (code "66") (name "unconnected-(IC5-PC9{slash}I2S2_CKIN{slash}I2S3_CKIN-Pad40)") (class "Default")
      (node (ref "IC5") (pin "40") (pinfunction "PC9/I2S2_CKIN/I2S3_CKIN_40") (pintype "bidirectional"))
    )
    (net (code "67") (name "unconnected-(IC5-PC12{slash}UART5_TX{slash}I2S3_SD{slash}USART3_CK-Pad53)") (class "Default")
      (node (ref "IC5") (pin "53") (pinfunction "PC12/UART5_TX/I2S3_SD/USART3_CK_53") (pintype "bidirectional"))
    )
    (net (code "68") (name "unconnected-(IC5-PC13-TAMPER-RTC-Pad2)") (class "Default")
      (node (ref "IC5") (pin "2") (pinfunction "PC13-TAMPER-RTC_2") (pintype "bidirectional"))
    )
    (net (code "69") (name "unconnected-(IC5-PC14{slash}OSC32_IN-Pad3)") (class "Default")
      (node (ref "IC5") (pin "3") (pinfunction "PC14/OSC32_IN_3") (pintype "bidirectional"))
    )
    (net (code "70") (name "unconnected-(IC5-PC15{slash}OSC_OUT-Pad4)") (class "Default")
      (node (ref "IC5") (pin "4") (pinfunction "PC15/OSC_OUT_4") (pintype "bidirectional"))
    )
    (net (code "71") (name "unconnected-(IC5-PD2{slash}TIM3-ETR-Pad54)") (class "Default")
      (node (ref "IC5") (pin "54") (pinfunction "PD2/TIM3-ETR_54") (pintype "bidirectional"))
    )
    (net (code "72") (name "unconnected-(IC8-CLKOUT-Pad2)") (class "Default")
      (node (ref "IC8") (pin "2") (pinfunction "CLKOUT_2") (pintype "bidirectional"))
    )
    (net (code "73") (name "unconnected-(IC8-LHPOUT-Pad9)") (class "Default")
      (node (ref "IC8") (pin "9") (pinfunction "LHPOUT_9") (pintype "bidirectional"))
    )
    (net (code "74") (name "unconnected-(IC8-MICBIAS-Pad17)") (class "Default")
      (node (ref "IC8") (pin "17") (pinfunction "MICBIAS_17") (pintype "bidirectional"))
    )
    (net (code "75") (name "unconnected-(IC8-MICIN-Pad18)") (class "Default")
      (node (ref "IC8") (pin "18") (pinfunction "MICIN_18") (pintype "bidirectional"))
    )
    (net (code "76") (name "unconnected-(IC8-RHPOUT-Pad10)") (class "Default")
      (node (ref "IC8") (pin "10") (pinfunction "RHPOUT_10") (pintype "bidirectional"))
    )
    (net (code "77") (name "unconnected-(JP1-Pad2)") (class "Default")
      (node (ref "JP1") (pin "2") (pinfunction "2_2") (pintype "passive"))
    )
    (net (code "78") (name "unconnected-(JP1-Pad3)") (class "Default")
      (node (ref "JP1") (pin "3") (pinfunction "3_3") (pintype "passive"))
    )
    (net (code "79") (name "unconnected-(JP1-Pad6)") (class "Default")
      (node (ref "JP1") (pin "6") (pinfunction "6_6") (pintype "passive"))
    )
    (net (code "80") (name "unconnected-(JP2-Pad7)") (class "Default")
      (node (ref "JP2") (pin "7") (pinfunction "7_7") (pintype "passive"))
    )
    (net (code "81") (name "unconnected-(JP70-Pad3)") (class "Default")
      (node (ref "JP70") (pin "3") (pinfunction "3_3") (pintype "passive"))
    )
  )
)
